# 03_Mode_Inputs.net
KiCad netlist of a schematic drawn in Altium Designer
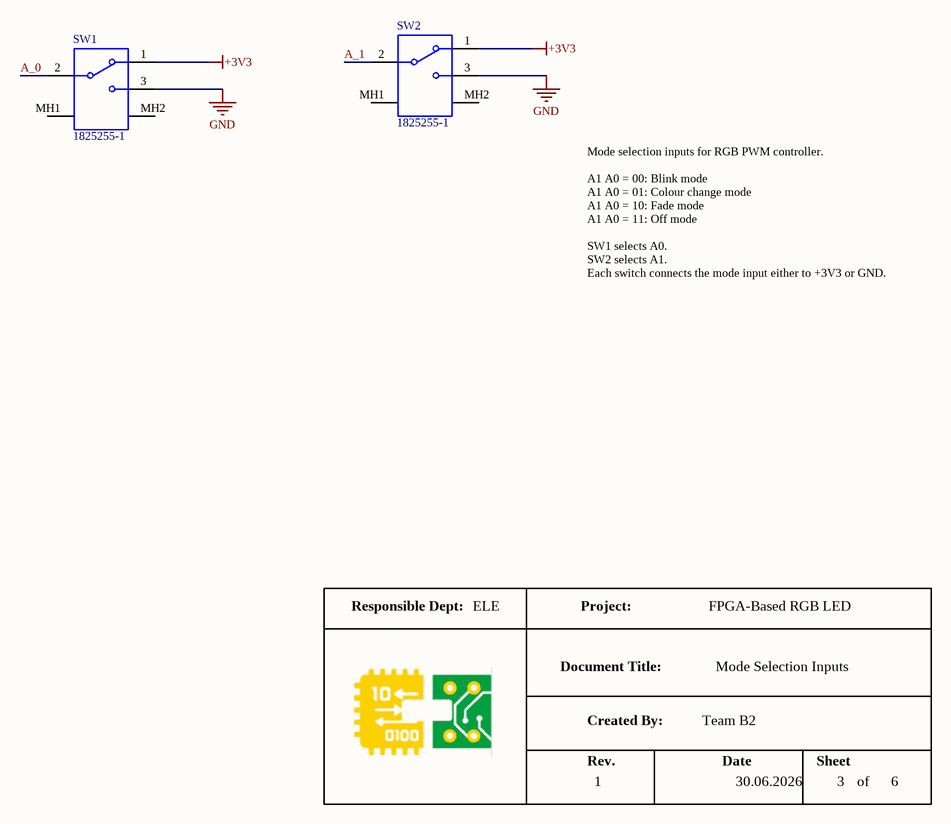
[diagram p0: 03_Mode_Inputs.SchDoc]

(export (version "E")
  (design (tool "Eeschema 10.0.6"))
  (components
    (comp (ref "SW1")
      (value "1825255-1")
      (footprint "TECO-1825255-1_V")
      (description "Slide Switch, SPDT, 0.3A, 125 V, -20 to 85 degC, 5-Pin THD, RoHS, Tray")
      (fields (field (name "MANUFACTURER") "TE Connectivity"))
      (libsource (lib "Hany Chowdhury") (part "SW-SPDT-3_C"))
    )
    (comp (ref "SW2")
      (value "1825255-1")
      (footprint "TECO-1825255-1_V")
      (description "Slide Switch, SPDT, 0.3A, 125 V, -20 to 85 degC, 5-Pin THD, RoHS, Tray")
      (fields (field (name "MANUFACTURER") "TE Connectivity"))
      (libsource (lib "Hany Chowdhury") (part "SW-SPDT-3_C"))
    )
  )
  (nets
    (net (code "1") (name "+3V3") (class "Default")
      (node (ref "SW1") (pin "1") (pinfunction "1_1") (pintype "passive"))
      (node (ref "SW2") (pin "1") (pinfunction "1_1") (pintype "passive"))
    )
    (net (code "2") (name "/A_0") (class "Default")
      (node (ref "SW1") (pin "2") (pinfunction "2_2") (pintype "passive"))
    )
    (net (code "3") (name "/A_1") (class "Default")
      (node (ref "SW2") (pin "2") (pinfunction "2_2") (pintype "passive"))
    )
    (net (code "4") (name "GND") (class "Default")
      (node (ref "SW1") (pin "3") (pinfunction "3_3") (pintype "passive"))
      (node (ref "SW2") (pin "3") (pinfunction "3_3") (pintype "passive"))
    )
    (net (code "5") (name "unconnected-(SW1-PadMH1)") (class "Default")
      (node (ref "SW1") (pin "MH1") (pinfunction "MH1_MH1") (pintype "passive"))
    )
    (net (code "6") (name "unconnected-(SW1-PadMH2)") (class "Default")
      (node (ref "SW1") (pin "MH2") (pinfunction "MH2_MH2") (pintype "passive"))
    )
    (net (code "7") (name "unconnected-(SW2-PadMH1)") (class "Default")
      (node (ref "SW2") (pin "MH1") (pinfunction "MH1_MH1") (pintype "passive"))
    )
    (net (code "8") (name "unconnected-(SW2-PadMH2)") (class "Default")
      (node (ref "SW2") (pin "MH2") (pinfunction "MH2_MH2") (pintype "passive"))
    )
  )
)
